# v4_0.net
KiCad netlist of a schematic drawn in EAGLE
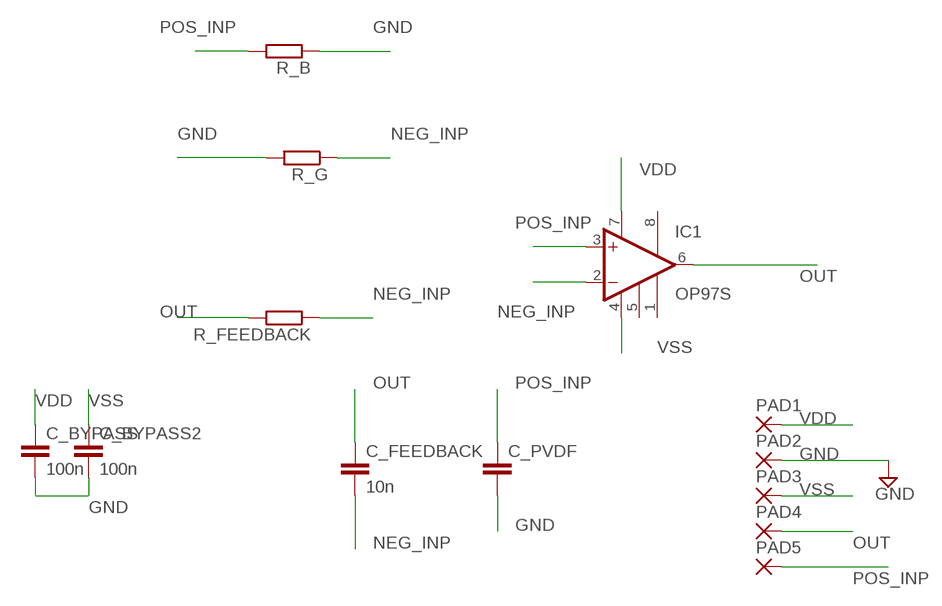
[diagram p0: schematic, sheet 1]

(export (version "E")
  (design (tool "Eeschema 10.0.6"))
  (components
    (comp (ref "C_BYPASS")
      (value "100n")
      (footprint "eagle-import:C0805")
      (libsource (lib "eagle-import") (part "resistor_348_C-EUC0805"))
    )
    (comp (ref "C_BYPASS2")
      (value "100n")
      (footprint "eagle-import:C0805")
      (libsource (lib "eagle-import") (part "resistor_348_C-EUC0805"))
    )
    (comp (ref "C_FEEDBACK")
      (value "10n")
      (footprint "eagle-import:C0805")
      (libsource (lib "eagle-import") (part "C-EUC0805"))
    )
    (comp (ref "C_PVDF")
      (value "C-EUC0805")
      (footprint "eagle-import:C0805")
      (libsource (lib "eagle-import") (part "C-EUC0805"))
    )
    (comp (ref "IC1")
      (value "OP97S")
      (footprint "eagle-import:SO08")
      (libsource (lib "eagle-import") (part "OP97S"))
    )
    (comp (ref "PAD1")
      (value "SMD5")
      (footprint "eagle-import:SMD2,54-5,08")
      (libsource (lib "eagle-import") (part "SMD5"))
    )
    (comp (ref "PAD2")
      (value "SMD5")
      (footprint "eagle-import:SMD2,54-5,08")
      (libsource (lib "eagle-import") (part "SMD5"))
    )
    (comp (ref "PAD3")
      (value "SMD5")
      (footprint "eagle-import:SMD2,54-5,08")
      (libsource (lib "eagle-import") (part "SMD5"))
    )
    (comp (ref "PAD4")
      (value "SMD5")
      (footprint "eagle-import:SMD2,54-5,08")
      (libsource (lib "eagle-import") (part "SMD5"))
    )
    (comp (ref "PAD5")
      (value "SMD5")
      (footprint "eagle-import:SMD2,54-5,08")
      (libsource (lib "eagle-import") (part "SMD5"))
    )
    (comp (ref "R_B")
      (value "100M")
      (footprint "eagle-import:M0805")
      (libsource (lib "eagle-import") (part "R-EU_M0805"))
    )
    (comp (ref "R_FEEDBACK")
      (value "200k")
      (footprint "eagle-import:M0805")
      (libsource (lib "eagle-import") (part "R-EU_M0805"))
    )
    (comp (ref "R_G")
      (value "10k")
      (footprint "eagle-import:M0805")
      (libsource (lib "eagle-import") (part "R-EU_M0805"))
    )
  )
  (nets
    (net (code "1") (name "/NEG_INP") (class "Default")
      (node (ref "C_FEEDBACK") (pin "2") (pinfunction "2_2") (pintype "passive"))
      (node (ref "IC1") (pin "2") (pinfunction "-IN_2") (pintype "input"))
      (node (ref "R_FEEDBACK") (pin "1") (pinfunction "1_1") (pintype "passive"))
      (node (ref "R_G") (pin "1") (pinfunction "1_1") (pintype "passive"))
    )
    (net (code "2") (name "/OUT") (class "Default")
      (node (ref "C_FEEDBACK") (pin "1") (pinfunction "1_1") (pintype "passive"))
      (node (ref "IC1") (pin "6") (pinfunction "OUT_6") (pintype "output"))
      (node (ref "PAD4") (pin "1") (pinfunction "P_1") (pintype "passive"))
      (node (ref "R_FEEDBACK") (pin "2") (pinfunction "2_2") (pintype "passive"))
    )
    (net (code "3") (name "/POS_INP") (class "Default")
      (node (ref "C_PVDF") (pin "1") (pinfunction "1_1") (pintype "passive"))
      (node (ref "IC1") (pin "3") (pinfunction "+IN_3") (pintype "input"))
      (node (ref "PAD5") (pin "1") (pinfunction "P_1") (pintype "passive"))
      (node (ref "R_B") (pin "2") (pinfunction "2_2") (pintype "passive"))
    )
    (net (code "4") (name "/VDD") (class "Default")
      (node (ref "C_BYPASS") (pin "1") (pinfunction "1_1") (pintype "passive"))
      (node (ref "IC1") (pin "7") (pinfunction "V+_7") (pintype "power_in"))
      (node (ref "PAD1") (pin "1") (pinfunction "P_1") (pintype "passive"))
    )
    (net (code "5") (name "/VSS") (class "Default")
      (node (ref "C_BYPASS2") (pin "1") (pinfunction "1_1") (pintype "passive"))
      (node (ref "IC1") (pin "4") (pinfunction "V-_4") (pintype "power_in"))
      (node (ref "PAD3") (pin "1") (pinfunction "P_1") (pintype "passive"))
    )
    (net (code "6") (name "GND") (class "Default")
      (node (ref "C_BYPASS") (pin "2") (pinfunction "2_2") (pintype "passive"))
      (node (ref "C_BYPASS2") (pin "2") (pinfunction "2_2") (pintype "passive"))
      (node (ref "C_PVDF") (pin "2") (pinfunction "2_2") (pintype "passive"))
      (node (ref "PAD2") (pin "1") (pinfunction "P_1") (pintype "passive"))
      (node (ref "R_B") (pin "1") (pinfunction "1_1") (pintype "passive"))
      (node (ref "R_G") (pin "2") (pinfunction "2_2") (pintype "passive"))
    )
    (net (code "7") (name "unconnected-(IC1-BAL1-Pad1)") (class "Default")
      (node (ref "IC1") (pin "1") (pinfunction "BAL1_1") (pintype "passive"))
    )
    (net (code "8") (name "unconnected-(IC1-BAL2-Pad8)") (class "Default")
      (node (ref "IC1") (pin "8") (pinfunction "BAL2_8") (pintype "passive"))
    )
    (net (code "9") (name "unconnected-(IC1-COMP-Pad5)") (class "Default")
      (node (ref "IC1") (pin "5") (pinfunction "COMP_5") (pintype "passive"))
    )
  )
)
